# snowflake.net
KiCad netlist of a schematic drawn in EAGLE
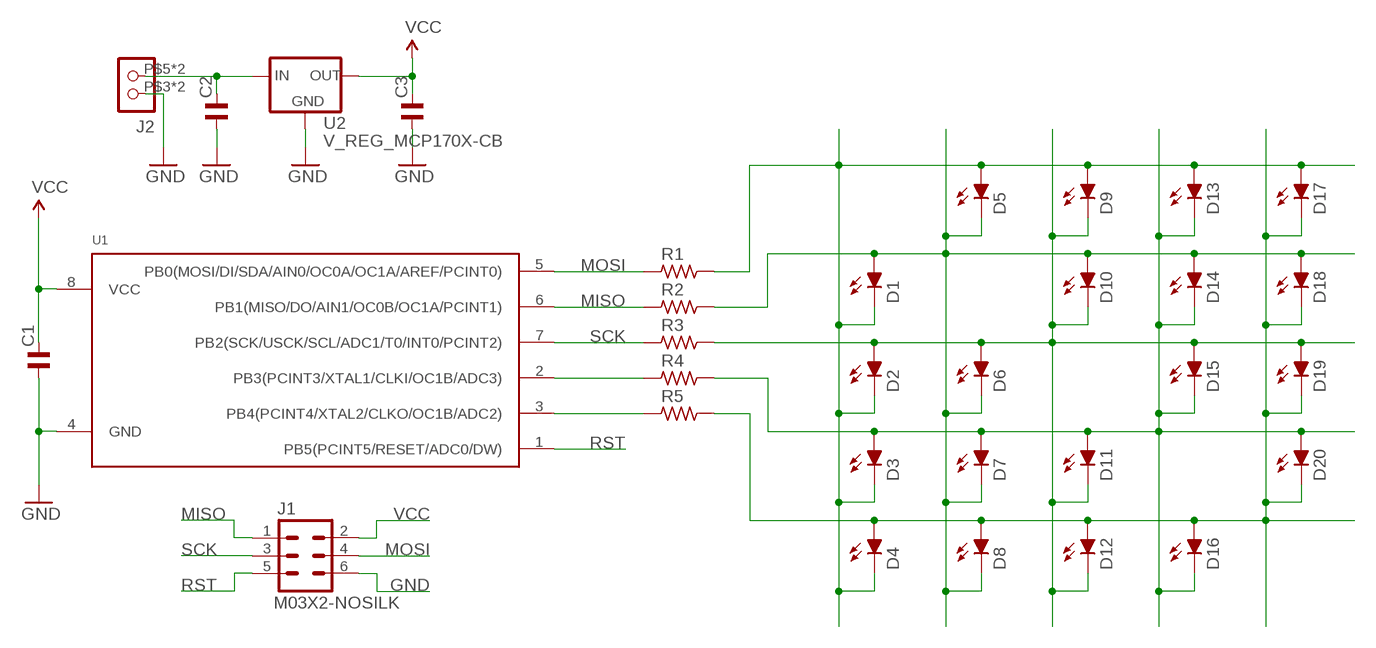
[diagram p0: schematic, sheet 1]

(export (version "E")
  (design (tool "Eeschema 10.0.6"))
  (components
    (comp (ref "C1")
      (value "C_0805NOSILK")
      (footprint "eagle-import:C0805NOSILK")
      (libsource (lib "eagle-import") (part "C_0805NOSILK"))
    )
    (comp (ref "C2")
      (value "C_0805NOSILK")
      (footprint "eagle-import:C0805NOSILK")
      (libsource (lib "eagle-import") (part "C_0805NOSILK"))
    )
    (comp (ref "C3")
      (value "C_0805NOSILK")
      (footprint "eagle-import:C0805NOSILK")
      (libsource (lib "eagle-import") (part "C_0805NOSILK"))
    )
    (comp (ref "D1")
      (value "LEDCHIP-LED0805NOSILK")
      (footprint "eagle-import:CHIP-LED0805NOSILK")
      (libsource (lib "eagle-import") (part "LEDCHIP-LED0805NOSILK"))
    )
    (comp (ref "D2")
      (value "LEDCHIP-LED0805NOSILK")
      (footprint "eagle-import:CHIP-LED0805NOSILK")
      (libsource (lib "eagle-import") (part "LEDCHIP-LED0805NOSILK"))
    )
    (comp (ref "D3")
      (value "LEDCHIP-LED0805NOSILK")
      (footprint "eagle-import:CHIP-LED0805NOSILK")
      (libsource (lib "eagle-import") (part "LEDCHIP-LED0805NOSILK"))
    )
    (comp (ref "D4")
      (value "LEDCHIP-LED0805NOSILK")
      (footprint "eagle-import:CHIP-LED0805NOSILK")
      (libsource (lib "eagle-import") (part "LEDCHIP-LED0805NOSILK"))
    )
    (comp (ref "D5")
      (value "LEDCHIP-LED0805NOSILK")
      (footprint "eagle-import:CHIP-LED0805NOSILK")
      (libsource (lib "eagle-import") (part "LEDCHIP-LED0805NOSILK"))
    )
    (comp (ref "D6")
      (value "LEDCHIP-LED0805NOSILK")
      (footprint "eagle-import:CHIP-LED0805NOSILK")
      (libsource (lib "eagle-import") (part "LEDCHIP-LED0805NOSILK"))
    )
    (comp (ref "D7")
      (value "LEDCHIP-LED0805NOSILK")
      (footprint "eagle-import:CHIP-LED0805NOSILK")
      (libsource (lib "eagle-import") (part "LEDCHIP-LED0805NOSILK"))
    )
    (comp (ref "D8")
      (value "LEDCHIP-LED0805NOSILK")
      (footprint "eagle-import:CHIP-LED0805NOSILK")
      (libsource (lib "eagle-import") (part "LEDCHIP-LED0805NOSILK"))
    )
    (comp (ref "D9")
      (value "LEDCHIP-LED0805NOSILK")
      (footprint "eagle-import:CHIP-LED0805NOSILK")
      (libsource (lib "eagle-import") (part "LEDCHIP-LED0805NOSILK"))
    )
    (comp (ref "D10")
      (value "LEDCHIP-LED0805NOSILK")
      (footprint "eagle-import:CHIP-LED0805NOSILK")
      (libsource (lib "eagle-import") (part "LEDCHIP-LED0805NOSILK"))
    )
    (comp (ref "D11")
      (value "LEDCHIP-LED0805NOSILK")
      (footprint "eagle-import:CHIP-LED0805NOSILK")
      (libsource (lib "eagle-import") (part "LEDCHIP-LED0805NOSILK"))
    )
    (comp (ref "D12")
      (value "LEDCHIP-LED0805NOSILK")
      (footprint "eagle-import:CHIP-LED0805NOSILK")
      (libsource (lib "eagle-import") (part "LEDCHIP-LED0805NOSILK"))
    )
    (comp (ref "D13")
      (value "LEDCHIP-LED0805NOSILK")
      (footprint "eagle-import:CHIP-LED0805NOSILK")
      (libsource (lib "eagle-import") (part "LEDCHIP-LED0805NOSILK"))
    )
    (comp (ref "D14")
      (value "LEDCHIP-LED0805NOSILK")
      (footprint "eagle-import:CHIP-LED0805NOSILK")
      (libsource (lib "eagle-import") (part "LEDCHIP-LED0805NOSILK"))
    )
    (comp (ref "D15")
      (value "LEDCHIP-LED0805NOSILK")
      (footprint "eagle-import:CHIP-LED0805NOSILK")
      (libsource (lib "eagle-import") (part "LEDCHIP-LED0805NOSILK"))
    )
    (comp (ref "D16")
      (value "LEDCHIP-LED0805NOSILK")
      (footprint "eagle-import:CHIP-LED0805NOSILK")
      (libsource (lib "eagle-import") (part "LEDCHIP-LED0805NOSILK"))
    )
    (comp (ref "D17")
      (value "LEDCHIP-LED0805NOSILK")
      (footprint "eagle-import:CHIP-LED0805NOSILK")
      (libsource (lib "eagle-import") (part "LEDCHIP-LED0805NOSILK"))
    )
    (comp (ref "D18")
      (value "LEDCHIP-LED0805NOSILK")
      (footprint "eagle-import:CHIP-LED0805NOSILK")
      (libsource (lib "eagle-import") (part "LEDCHIP-LED0805NOSILK"))
    )
    (comp (ref "D19")
      (value "LEDCHIP-LED0805NOSILK")
      (footprint "eagle-import:CHIP-LED0805NOSILK")
      (libsource (lib "eagle-import") (part "LEDCHIP-LED0805NOSILK"))
    )
    (comp (ref "D20")
      (value "LEDCHIP-LED0805NOSILK")
      (footprint "eagle-import:CHIP-LED0805NOSILK")
      (libsource (lib "eagle-import") (part "LEDCHIP-LED0805NOSILK"))
    )
    (comp (ref "J1")
      (value "M03X2-NOSILK")
      (footprint "eagle-import:2X03_LOCK_NOSILK")
      (libsource (lib "eagle-import") (part "M03X2-NOSILK"))
    )
    (comp (ref "J2")
      (value "CON_TERMINAL_HOLES")
      (footprint "eagle-import:TERMINAL_2P_4H")
      (libsource (lib "eagle-import") (part "CON_TERMINAL_HOLES"))
    )
    (comp (ref "R1")
      (value "R_0805NOSILK")
      (footprint "eagle-import:R0805NOSILK")
      (libsource (lib "eagle-import") (part "R_0805NOSILK"))
    )
    (comp (ref "R2")
      (value "R_0805NOSILK")
      (footprint "eagle-import:R0805NOSILK")
      (libsource (lib "eagle-import") (part "R_0805NOSILK"))
    )
    (comp (ref "R3")
      (value "R_0805NOSILK")
      (footprint "eagle-import:R0805NOSILK")
      (libsource (lib "eagle-import") (part "R_0805NOSILK"))
    )
    (comp (ref "R4")
      (value "R_0805NOSILK")
      (footprint "eagle-import:R0805NOSILK")
      (libsource (lib "eagle-import") (part "R_0805NOSILK"))
    )
    (comp (ref "R5")
      (value "R_0805NOSILK")
      (footprint "eagle-import:R0805NOSILK")
      (libsource (lib "eagle-import") (part "R_0805NOSILK"))
    )
    (comp (ref "U1")
      (value "ATTINY5-20SU-NOSILK")
      (footprint "eagle-import:SOP8-8S2-NOSILK")
      (libsource (lib "eagle-import") (part "ATTINY5-20SU-NOSILK"))
    )
    (comp (ref "U2")
      (value "V_REG_MCP170X-CB")
      (footprint "eagle-import:SOT23")
      (libsource (lib "eagle-import") (part "V_REG_MCP170X-CB"))
    )
  )
  (nets
    (net (code "1") (name "/MISO") (class "Default")
      (node (ref "J1") (pin "1") (pinfunction "1_1") (pintype "passive"))
      (node (ref "R2") (pin "1") (pinfunction "1_1") (pintype "passive"))
      (node (ref "U1") (pin "6") (pinfunction "PB1(MISO/DO/AIN1/OC0B/OC1A/PCINT1)_6") (pintype "bidirectional"))
    )
    (net (code "2") (name "/MOSI") (class "Default")
      (node (ref "J1") (pin "4") (pinfunction "4_4") (pintype "passive"))
      (node (ref "R1") (pin "1") (pinfunction "1_1") (pintype "passive"))
      (node (ref "U1") (pin "5") (pinfunction "PB0(MOSI/DI/SDA/AIN0/OC0A/OC1A/AREF/PCINT0)_5") (pintype "bidirectional"))
    )
    (net (code "3") (name "/RST") (class "Default")
      (node (ref "J1") (pin "5") (pinfunction "5_5") (pintype "passive"))
      (node (ref "U1") (pin "1") (pinfunction "PB5(PCINT5/RESET/ADC0/DW)_1") (pintype "bidirectional"))
    )
    (net (code "4") (name "/SCK") (class "Default")
      (node (ref "J1") (pin "3") (pinfunction "3_3") (pintype "passive"))
      (node (ref "R3") (pin "1") (pinfunction "1_1") (pintype "passive"))
      (node (ref "U1") (pin "7") (pinfunction "PB2(SCK/USCK/SCL/ADC1/T0/INT0/PCINT2)_7") (pintype "bidirectional"))
    )
    (net (code "5") (name "GND") (class "Default")
      (node (ref "C1") (pin "1") (pinfunction "1_1") (pintype "passive"))
      (node (ref "C2") (pin "1") (pinfunction "1_1") (pintype "passive"))
      (node (ref "C3") (pin "1") (pinfunction "1_1") (pintype "passive"))
      (node (ref "J1") (pin "6") (pinfunction "6_6") (pintype "passive"))
      (node (ref "J2") (pin "P$3") (pinfunction "1_P$3") (pintype "passive"))
      (node (ref "J2") (pin "P$4") (pinfunction "1_P$4") (pintype "passive"))
      (node (ref "U1") (pin "4") (pinfunction "GND_4") (pintype "bidirectional"))
      (node (ref "U2") (pin "1") (pinfunction "GND_1") (pintype "input"))
    )
    (net (code "6") (name "Net-(D1-PadA)") (class "Default")
      (node (ref "D1") (pin "A") (pinfunction "A_A") (pintype "passive"))
      (node (ref "D10") (pin "A") (pinfunction "A_A") (pintype "passive"))
      (node (ref "D14") (pin "A") (pinfunction "A_A") (pintype "passive"))
      (node (ref "D18") (pin "A") (pinfunction "A_A") (pintype "passive"))
      (node (ref "D5") (pin "C") (pinfunction "C_C") (pintype "passive"))
      (node (ref "D6") (pin "C") (pinfunction "C_C") (pintype "passive"))
      (node (ref "D7") (pin "C") (pinfunction "C_C") (pintype "passive"))
      (node (ref "D8") (pin "C") (pinfunction "C_C") (pintype "passive"))
      (node (ref "R2") (pin "2") (pinfunction "2_2") (pintype "passive"))
    )
    (net (code "7") (name "Net-(D1-PadC)") (class "Default")
      (node (ref "D1") (pin "C") (pinfunction "C_C") (pintype "passive"))
      (node (ref "D13") (pin "A") (pinfunction "A_A") (pintype "passive"))
      (node (ref "D17") (pin "A") (pinfunction "A_A") (pintype "passive"))
      (node (ref "D2") (pin "C") (pinfunction "C_C") (pintype "passive"))
      (node (ref "D3") (pin "C") (pinfunction "C_C") (pintype "passive"))
      (node (ref "D4") (pin "C") (pinfunction "C_C") (pintype "passive"))
      (node (ref "D5") (pin "A") (pinfunction "A_A") (pintype "passive"))
      (node (ref "D9") (pin "A") (pinfunction "A_A") (pintype "passive"))
      (node (ref "R1") (pin "2") (pinfunction "2_2") (pintype "passive"))
    )
    (net (code "8") (name "Net-(D10-PadC)") (class "Default")
      (node (ref "D10") (pin "C") (pinfunction "C_C") (pintype "passive"))
      (node (ref "D11") (pin "C") (pinfunction "C_C") (pintype "passive"))
      (node (ref "D12") (pin "C") (pinfunction "C_C") (pintype "passive"))
      (node (ref "D15") (pin "A") (pinfunction "A_A") (pintype "passive"))
      (node (ref "D19") (pin "A") (pinfunction "A_A") (pintype "passive"))
      (node (ref "D2") (pin "A") (pinfunction "A_A") (pintype "passive"))
      (node (ref "D6") (pin "A") (pinfunction "A_A") (pintype "passive"))
      (node (ref "D9") (pin "C") (pinfunction "C_C") (pintype "passive"))
      (node (ref "R3") (pin "2") (pinfunction "2_2") (pintype "passive"))
    )
    (net (code "9") (name "Net-(D11-PadA)") (class "Default")
      (node (ref "D11") (pin "A") (pinfunction "A_A") (pintype "passive"))
      (node (ref "D13") (pin "C") (pinfunction "C_C") (pintype "passive"))
      (node (ref "D14") (pin "C") (pinfunction "C_C") (pintype "passive"))
      (node (ref "D15") (pin "C") (pinfunction "C_C") (pintype "passive"))
      (node (ref "D16") (pin "C") (pinfunction "C_C") (pintype "passive"))
      (node (ref "D20") (pin "A") (pinfunction "A_A") (pintype "passive"))
      (node (ref "D3") (pin "A") (pinfunction "A_A") (pintype "passive"))
      (node (ref "D7") (pin "A") (pinfunction "A_A") (pintype "passive"))
      (node (ref "R4") (pin "2") (pinfunction "2_2") (pintype "passive"))
    )
    (net (code "10") (name "Net-(D12-PadA)") (class "Default")
      (node (ref "D12") (pin "A") (pinfunction "A_A") (pintype "passive"))
      (node (ref "D16") (pin "A") (pinfunction "A_A") (pintype "passive"))
      (node (ref "D17") (pin "C") (pinfunction "C_C") (pintype "passive"))
      (node (ref "D18") (pin "C") (pinfunction "C_C") (pintype "passive"))
      (node (ref "D19") (pin "C") (pinfunction "C_C") (pintype "passive"))
      (node (ref "D20") (pin "C") (pinfunction "C_C") (pintype "passive"))
      (node (ref "D4") (pin "A") (pinfunction "A_A") (pintype "passive"))
      (node (ref "D8") (pin "A") (pinfunction "A_A") (pintype "passive"))
      (node (ref "R5") (pin "2") (pinfunction "2_2") (pintype "passive"))
    )
    (net (code "11") (name "Net-(U1-PB3(PCINT3{slash}XTAL1{slash}CLKI{slash}OC1B{slash}ADC3))") (class "Default")
      (node (ref "R4") (pin "1") (pinfunction "1_1") (pintype "passive"))
      (node (ref "U1") (pin "2") (pinfunction "PB3(PCINT3/XTAL1/CLKI/OC1B/ADC3)_2") (pintype "bidirectional"))
    )
    (net (code "12") (name "Net-(U1-PB4(PCINT4{slash}XTAL2{slash}CLKO{slash}OC1B{slash}ADC2))") (class "Default")
      (node (ref "R5") (pin "1") (pinfunction "1_1") (pintype "passive"))
      (node (ref "U1") (pin "3") (pinfunction "PB4(PCINT4/XTAL2/CLKO/OC1B/ADC2)_3") (pintype "bidirectional"))
    )
    (net (code "13") (name "Net-(U2-IN)") (class "Default")
      (node (ref "C2") (pin "2") (pinfunction "2_2") (pintype "passive"))
      (node (ref "J2") (pin "P$5") (pinfunction "2_P$5") (pintype "passive"))
      (node (ref "J2") (pin "P$6") (pinfunction "2_P$6") (pintype "passive"))
      (node (ref "U2") (pin "3") (pinfunction "IN_3") (pintype "input"))
    )
    (net (code "14") (name "VCC") (class "Default")
      (node (ref "C1") (pin "2") (pinfunction "2_2") (pintype "passive"))
      (node (ref "C3") (pin "2") (pinfunction "2_2") (pintype "passive"))
      (node (ref "J1") (pin "2") (pinfunction "2_2") (pintype "passive"))
      (node (ref "U1") (pin "8") (pinfunction "VCC_8") (pintype "bidirectional"))
      (node (ref "U2") (pin "2") (pinfunction "OUT_2") (pintype "power_in"))
    )
  )
)
